# E-28_Voltmeter.net
KiCad netlist of a schematic drawn in Altium Designer
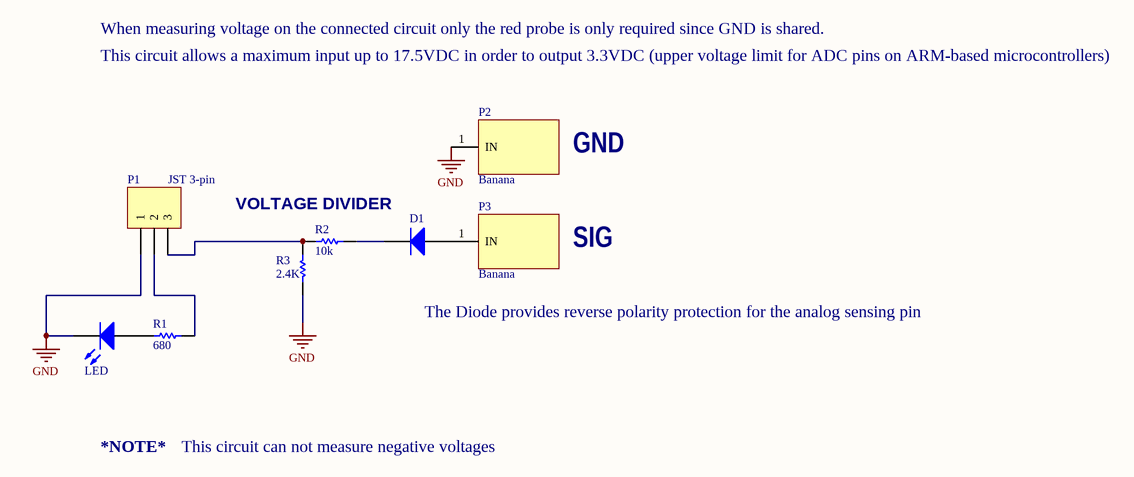
[diagram p0: E-28 Voltmeter.SchDoc]

(export (version "E")
  (design (tool "Eeschema 10.0.6"))
  (components
    (comp (ref "D1")
      (value "20V 1A")
      (footprint "DIODE SOD-123")
      (description "High Conductance Fast Diode")
      (fields (field (name "PUBLISHER") "Altium Limited"))
      (libsource (lib "Miscellaneous Devices") (part "Diode 1N4148"))
    )
    (comp (ref "LED")
      (value "LED2")
      (footprint "0805 LED - TIGHT")
      (description "Typical RED GaAs LED")
      (fields (field (name "PUBLISHER") "Altium Limited"))
      (libsource (lib "SB_Discrete") (part "LED1"))
    )
    (comp (ref "P1")
      (value "JST 3-pin")
      (footprint "JST-PH 3-pin SMD")
      (description "Header, 3-Pin")
      (fields (field (name "PUBLISHER") "Altium Limited"))
      (libsource (lib "Miscellaneous Connectors") (part "Header 3"))
    )
    (comp (ref "P2")
      (value "Banana")
      (footprint "Banana Jack RA")
      (libsource (lib "SB_Engineered_Components") (part "Banana Jack RA"))
    )
    (comp (ref "P3")
      (value "Banana")
      (footprint "Banana Jack RA")
      (libsource (lib "SB_Engineered_Components") (part "Banana Jack RA"))
    )
    (comp (ref "R1")
      (value "680")
      (footprint "0603 tight")
      (description "Resistor")
      (fields (field (name "Comment") "Res1") (field (name "PUBLISHER") "Altium Limited"))
      (libsource (lib "SB_Discrete") (part "Res1"))
    )
    (comp (ref "R2")
      (value "10k")
      (footprint "0603 tight")
      (description "Resistor")
      (fields (field (name "Comment") "Res1") (field (name "PUBLISHER") "Altium Limited"))
      (libsource (lib "SB_Discrete") (part "Res1"))
    )
    (comp (ref "R3")
      (value "2.4K")
      (footprint "0603 Tight")
      (description "Resistor")
      (fields (field (name "Comment") "Res1") (field (name "PUBLISHER") "Altium Limited"))
      (libsource (lib "SB_Discrete") (part "Res1"))
    )
  )
  (nets
    (net (code "1") (name "GND") (class "Default")
      (node (ref "LED") (pin "2") (pinfunction "K_2") (pintype "passive"))
      (node (ref "P1") (pin "1") (pinfunction "1_1") (pintype "passive"))
      (node (ref "P2") (pin "1") (pinfunction "IN_1") (pintype "passive"))
      (node (ref "R3") (pin "2") (pinfunction "2_2") (pintype "passive"))
    )
    (net (code "2") (name "Net-(D1-A)") (class "Default")
      (node (ref "D1") (pin "1") (pinfunction "A_1") (pintype "passive"))
      (node (ref "P3") (pin "1") (pinfunction "IN_1") (pintype "passive"))
    )
    (net (code "3") (name "Net-(D1-K)") (class "Default")
      (node (ref "D1") (pin "2") (pinfunction "K_2") (pintype "passive"))
      (node (ref "R2") (pin "2") (pinfunction "2_2") (pintype "passive"))
    )
    (net (code "4") (name "Net-(LED-A)") (class "Default")
      (node (ref "LED") (pin "1") (pinfunction "A_1") (pintype "passive"))
      (node (ref "R1") (pin "1") (pinfunction "1_1") (pintype "passive"))
    )
    (net (code "5") (name "Net-(P1-Pad2)") (class "Default")
      (node (ref "P1") (pin "2") (pinfunction "2_2") (pintype "passive"))
      (node (ref "R1") (pin "2") (pinfunction "2_2") (pintype "passive"))
    )
    (net (code "6") (name "Net-(P1-Pad3)") (class "Default")
      (node (ref "P1") (pin "3") (pinfunction "3_3") (pintype "passive"))
      (node (ref "R2") (pin "1") (pinfunction "1_1") (pintype "passive"))
      (node (ref "R3") (pin "1") (pinfunction "1_1") (pintype "passive"))
    )
  )
)
